# AD5679.net
KiCad netlist of a schematic drawn in Altium Designer
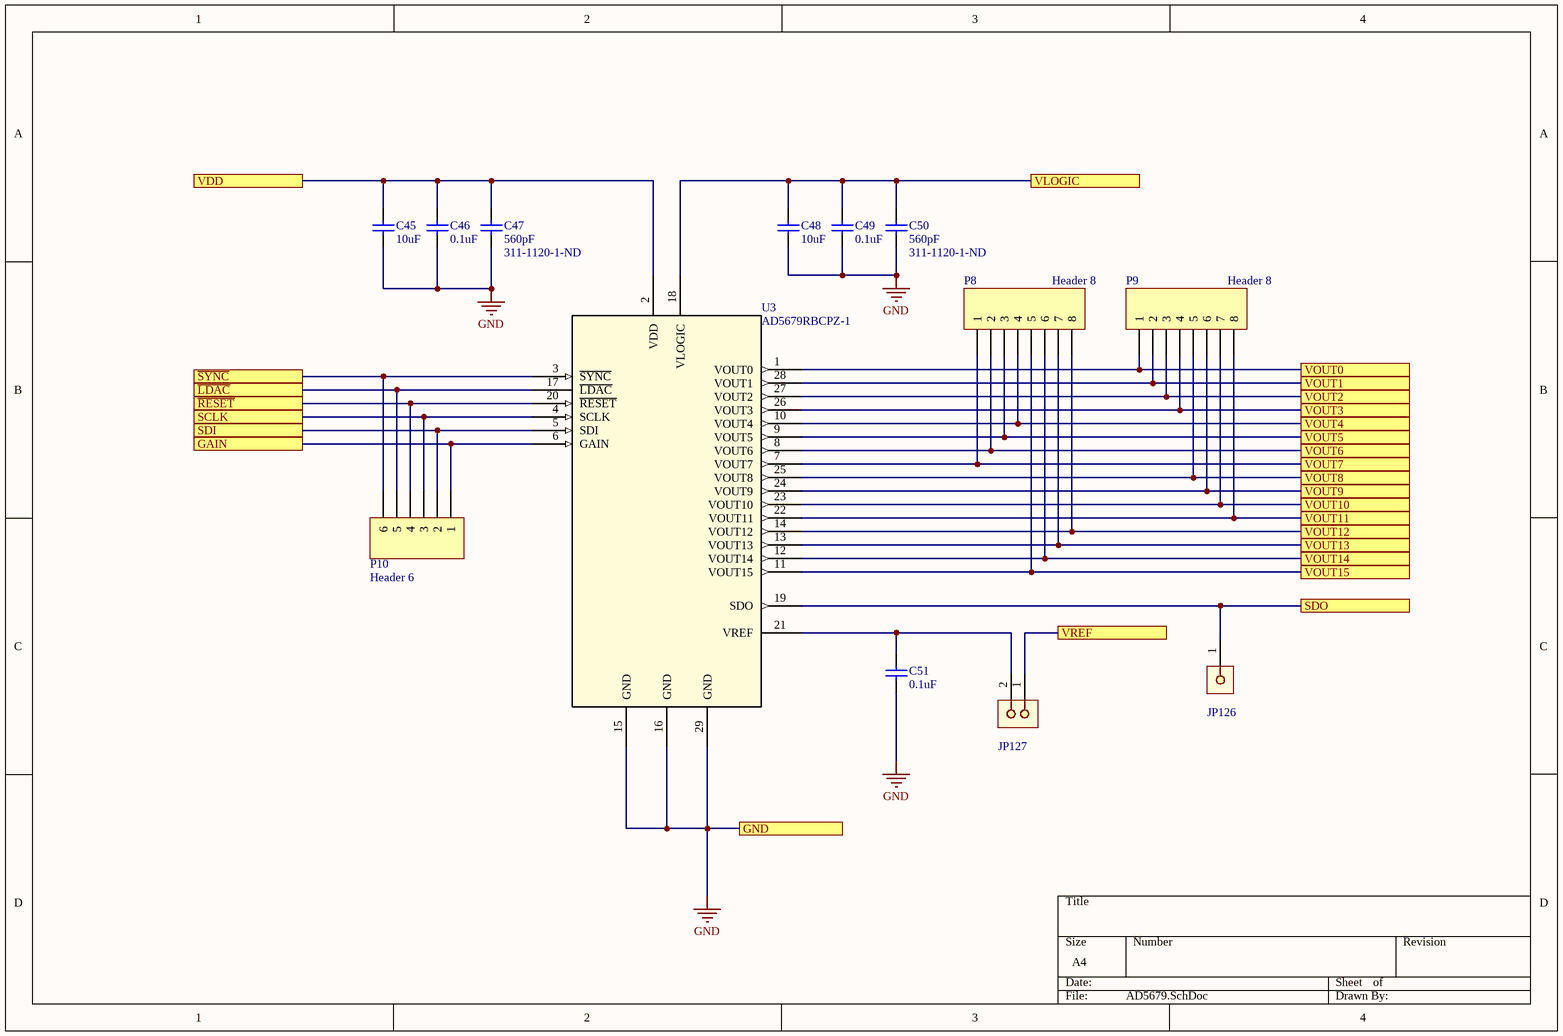
[diagram p0: AD5679.SchDoc]

(export (version "E")
  (design (tool "Eeschema 10.0.6"))
  (components
    (comp (ref "C45")
      (value "10uF")
      (footprint "CLS_Library:C0805")
      (description "Cap 10uF")
      (fields
        (field (name "MANUFACTURER") "Taiyo Yuden")
        (field (name "MANUFACTURER PART NUMBER") "UMK212SD103KD-T")
      )
      (libsource (lib "Chip1_TestBoard") (part "Cap 10uF"))
    )
    (comp (ref "C46")
      (value "0.1uF")
      (footprint "CLS_Library:C0805")
      (description "Cap 0.1uF")
      (fields
        (field (name "MANUFACTURER") "Taiyo Yuden")
        (field (name "MANUFACTURER PART NUMBER") "UMK212SD103KD-T")
      )
      (libsource (lib "Chip1_TestBoard") (part "Cap 0.1uF"))
    )
    (comp (ref "C47")
      (value "560pF")
      (footprint "CLS_Library:C0805")
      (description "Cap 560pF")
      (fields
        (field (name "MANUFACTURER") "Taiyo Yuden")
        (field (name "MANUFACTURER PART NUMBER") "UMK212SD103KD-T")
        (field (name "SUPPLIER PART NUMBER 1") "311-1120-1-ND")
      )
      (libsource (lib "Chip1_TestBoard") (part "Cap 560pF"))
    )
    (comp (ref "C48")
      (value "10uF")
      (footprint "CLS_Library:C0805")
      (description "Cap 10uF")
      (fields
        (field (name "MANUFACTURER") "Taiyo Yuden")
        (field (name "MANUFACTURER PART NUMBER") "UMK212SD103KD-T")
      )
      (libsource (lib "Chip1_TestBoard") (part "Cap 10uF"))
    )
    (comp (ref "C49")
      (value "0.1uF")
      (footprint "CLS_Library:C0805")
      (description "Cap 0.1uF")
      (fields
        (field (name "MANUFACTURER") "Taiyo Yuden")
        (field (name "MANUFACTURER PART NUMBER") "UMK212SD103KD-T")
      )
      (libsource (lib "Chip1_TestBoard") (part "Cap 0.1uF"))
    )
    (comp (ref "C50")
      (value "560pF")
      (footprint "CLS_Library:C0805")
      (description "Cap 560pF")
      (fields
        (field (name "MANUFACTURER") "Taiyo Yuden")
        (field (name "MANUFACTURER PART NUMBER") "UMK212SD103KD-T")
        (field (name "SUPPLIER PART NUMBER 1") "311-1120-1-ND")
      )
      (libsource (lib "Chip1_TestBoard") (part "Cap 560pF"))
    )
    (comp (ref "C51")
      (value "0.1uF")
      (footprint "CLS_Library:C0805")
      (description "Cap 0.1uF")
      (fields
        (field (name "MANUFACTURER") "Taiyo Yuden")
        (field (name "MANUFACTURER PART NUMBER") "UMK212SD103KD-T")
      )
      (libsource (lib "Chip1_TestBoard") (part "Cap 0.1uF"))
    )
    (comp (ref "JP126")
      (value "01x01")
      (footprint "01x01_0_0.1in_th_straight_b_nom")
      (description "01X01 generic terminal connector")
      (libsource (lib "Chip1_TestBoard") (part "01x01"))
    )
    (comp (ref "JP127")
      (value "01x02")
      (footprint "01x02_0.1in_th_straight_b_nom")
      (description "01X02 generic terminal connector")
      (libsource (lib "Chip1_TestBoard") (part "01x02"))
    )
    (comp (ref "P8")
      (value "Header 8")
      (footprint "HDR1X8")
      (description "Header, 8-Pin")
      (fields (field (name "PUBLISHER") "Altium Limited"))
      (libsource (lib "Miscellaneous Connectors") (part "Header 8"))
    )
    (comp (ref "P9")
      (value "Header 8")
      (footprint "HDR1X8")
      (description "Header, 8-Pin")
      (fields (field (name "PUBLISHER") "Altium Limited"))
      (libsource (lib "Miscellaneous Connectors") (part "Header 8"))
    )
    (comp (ref "P10")
      (value "Header 6")
      (footprint "HDR1X6")
      (description "Header, 6-Pin")
      (fields (field (name "PUBLISHER") "Altium Limited"))
      (libsource (lib "Miscellaneous Connectors") (part "Header 6"))
    )
    (comp (ref "U3")
      (value "AD5679RBCPZ-1")
      (footprint "AD5679RBCPZ-1")
      (description "No Description Available")
      (fields (field (name "COPYRIGHT") "Copyright (C) 2018 Accelerated Designs. All rights reserved"))
      (libsource (lib "Chip1_TestBoard") (part "AD5679RBCPZ-1"))
    )
  )
  (nets
    (net (code "1") (name "/GAIN") (class "Default")
      (node (ref "P10") (pin "1") (pinfunction "1_1") (pintype "passive"))
      (node (ref "U3") (pin "6") (pinfunction "GAIN_6") (pintype "input"))
    )
    (net (code "2") (name "/SCLK") (class "Default")
      (node (ref "P10") (pin "3") (pinfunction "3_3") (pintype "passive"))
      (node (ref "U3") (pin "4") (pinfunction "SCLK_4") (pintype "input"))
    )
    (net (code "3") (name "/SDI") (class "Default")
      (node (ref "P10") (pin "2") (pinfunction "2_2") (pintype "passive"))
      (node (ref "U3") (pin "5") (pinfunction "SDI_5") (pintype "input"))
    )
    (net (code "4") (name "/SDO") (class "Default")
      (node (ref "JP126") (pin "1") (pinfunction "1_1") (pintype "passive"))
      (node (ref "U3") (pin "19") (pinfunction "SDO_19") (pintype "output"))
    )
    (net (code "5") (name "/VDD") (class "Default")
      (node (ref "C45") (pin "2") (pinfunction "2_2") (pintype "passive"))
      (node (ref "C46") (pin "2") (pinfunction "2_2") (pintype "passive"))
      (node (ref "C47") (pin "2") (pinfunction "2_2") (pintype "passive"))
      (node (ref "U3") (pin "2") (pinfunction "VDD_2") (pintype "power_in"))
    )
    (net (code "6") (name "/VLOGIC") (class "Default")
      (node (ref "C48") (pin "2") (pinfunction "2_2") (pintype "passive"))
      (node (ref "C49") (pin "2") (pinfunction "2_2") (pintype "passive"))
      (node (ref "C50") (pin "2") (pinfunction "2_2") (pintype "passive"))
      (node (ref "U3") (pin "18") (pinfunction "VLOGIC_18") (pintype "power_in"))
    )
    (net (code "7") (name "/VOUT0") (class "Default")
      (node (ref "P9") (pin "1") (pinfunction "1_1") (pintype "passive"))
      (node (ref "U3") (pin "1") (pinfunction "VOUT0_1") (pintype "output"))
    )
    (net (code "8") (name "/VOUT1") (class "Default")
      (node (ref "P9") (pin "2") (pinfunction "2_2") (pintype "passive"))
      (node (ref "U3") (pin "28") (pinfunction "VOUT1_28") (pintype "output"))
    )
    (net (code "9") (name "/VOUT2") (class "Default")
      (node (ref "P9") (pin "3") (pinfunction "3_3") (pintype "passive"))
      (node (ref "U3") (pin "27") (pinfunction "VOUT2_27") (pintype "output"))
    )
    (net (code "10") (name "/VOUT3") (class "Default")
      (node (ref "P9") (pin "4") (pinfunction "4_4") (pintype "passive"))
      (node (ref "U3") (pin "26") (pinfunction "VOUT3_26") (pintype "output"))
    )
    (net (code "11") (name "/VOUT4") (class "Default")
      (node (ref "P8") (pin "4") (pinfunction "4_4") (pintype "passive"))
      (node (ref "U3") (pin "10") (pinfunction "VOUT4_10") (pintype "output"))
    )
    (net (code "12") (name "/VOUT5") (class "Default")
      (node (ref "P8") (pin "3") (pinfunction "3_3") (pintype "passive"))
      (node (ref "U3") (pin "9") (pinfunction "VOUT5_9") (pintype "output"))
    )
    (net (code "13") (name "/VOUT6") (class "Default")
      (node (ref "P8") (pin "2") (pinfunction "2_2") (pintype "passive"))
      (node (ref "U3") (pin "8") (pinfunction "VOUT6_8") (pintype "output"))
    )
    (net (code "14") (name "/VOUT7") (class "Default")
      (node (ref "P8") (pin "1") (pinfunction "1_1") (pintype "passive"))
      (node (ref "U3") (pin "7") (pinfunction "VOUT7_7") (pintype "output"))
    )
    (net (code "15") (name "/VOUT8") (class "Default")
      (node (ref "P9") (pin "5") (pinfunction "5_5") (pintype "passive"))
      (node (ref "U3") (pin "25") (pinfunction "VOUT8_25") (pintype "output"))
    )
    (net (code "16") (name "/VOUT9") (class "Default")
      (node (ref "P9") (pin "6") (pinfunction "6_6") (pintype "passive"))
      (node (ref "U3") (pin "24") (pinfunction "VOUT9_24") (pintype "output"))
    )
    (net (code "17") (name "/VOUT10") (class "Default")
      (node (ref "P9") (pin "7") (pinfunction "7_7") (pintype "passive"))
      (node (ref "U3") (pin "23") (pinfunction "VOUT10_23") (pintype "output"))
    )
    (net (code "18") (name "/VOUT11") (class "Default")
      (node (ref "P9") (pin "8") (pinfunction "8_8") (pintype "passive"))
      (node (ref "U3") (pin "22") (pinfunction "VOUT11_22") (pintype "output"))
    )
    (net (code "19") (name "/VOUT12") (class "Default")
      (node (ref "P8") (pin "8") (pinfunction "8_8") (pintype "passive"))
      (node (ref "U3") (pin "14") (pinfunction "VOUT12_14") (pintype "output"))
    )
    (net (code "20") (name "/VOUT13") (class "Default")
      (node (ref "P8") (pin "7") (pinfunction "7_7") (pintype "passive"))
      (node (ref "U3") (pin "13") (pinfunction "VOUT13_13") (pintype "output"))
    )
    (net (code "21") (name "/VOUT14") (class "Default")
      (node (ref "P8") (pin "6") (pinfunction "6_6") (pintype "passive"))
      (node (ref "U3") (pin "12") (pinfunction "VOUT14_12") (pintype "output"))
    )
    (net (code "22") (name "/VOUT15") (class "Default")
      (node (ref "P8") (pin "5") (pinfunction "5_5") (pintype "passive"))
      (node (ref "U3") (pin "11") (pinfunction "VOUT15_11") (pintype "output"))
    )
    (net (code "23") (name "/VREF") (class "Default")
      (node (ref "JP127") (pin "1") (pinfunction "1_1") (pintype "passive"))
    )
    (net (code "24") (name "/~{LDAC}") (class "Default")
      (node (ref "P10") (pin "5") (pinfunction "5_5") (pintype "passive"))
      (node (ref "U3") (pin "17") (pinfunction "~{LDAC}_17") (pintype "passive"))
    )
    (net (code "25") (name "/~{RESET}") (class "Default")
      (node (ref "P10") (pin "4") (pinfunction "4_4") (pintype "passive"))
      (node (ref "U3") (pin "20") (pinfunction "~{RESET}_20") (pintype "input"))
    )
    (net (code "26") (name "/~{SYNC}") (class "Default")
      (node (ref "P10") (pin "6") (pinfunction "6_6") (pintype "passive"))
      (node (ref "U3") (pin "3") (pinfunction "~{SYNC}_3") (pintype "input"))
    )
    (net (code "27") (name "GND") (class "Default")
      (node (ref "C45") (pin "1") (pinfunction "1_1") (pintype "passive"))
      (node (ref "C46") (pin "1") (pinfunction "1_1") (pintype "passive"))
      (node (ref "C47") (pin "1") (pinfunction "1_1") (pintype "passive"))
      (node (ref "C48") (pin "1") (pinfunction "1_1") (pintype "passive"))
      (node (ref "C49") (pin "1") (pinfunction "1_1") (pintype "passive"))
      (node (ref "C50") (pin "1") (pinfunction "1_1") (pintype "passive"))
      (node (ref "C51") (pin "1") (pinfunction "1_1") (pintype "passive"))
      (node (ref "U3") (pin "15") (pinfunction "GND_15") (pintype "passive"))
      (node (ref "U3") (pin "16") (pinfunction "GND_16") (pintype "passive"))
      (node (ref "U3") (pin "29") (pinfunction "GND_29") (pintype "passive"))
    )
    (net (code "28") (name "Net-(U3-VREF)") (class "Default")
      (node (ref "C51") (pin "2") (pinfunction "2_2") (pintype "passive"))
      (node (ref "JP127") (pin "2") (pinfunction "2_2") (pintype "passive"))
      (node (ref "U3") (pin "21") (pinfunction "VREF_21") (pintype "power_in"))
    )
  )
)
